# addonv2.net
KiCad netlist of a schematic drawn in EAGLE
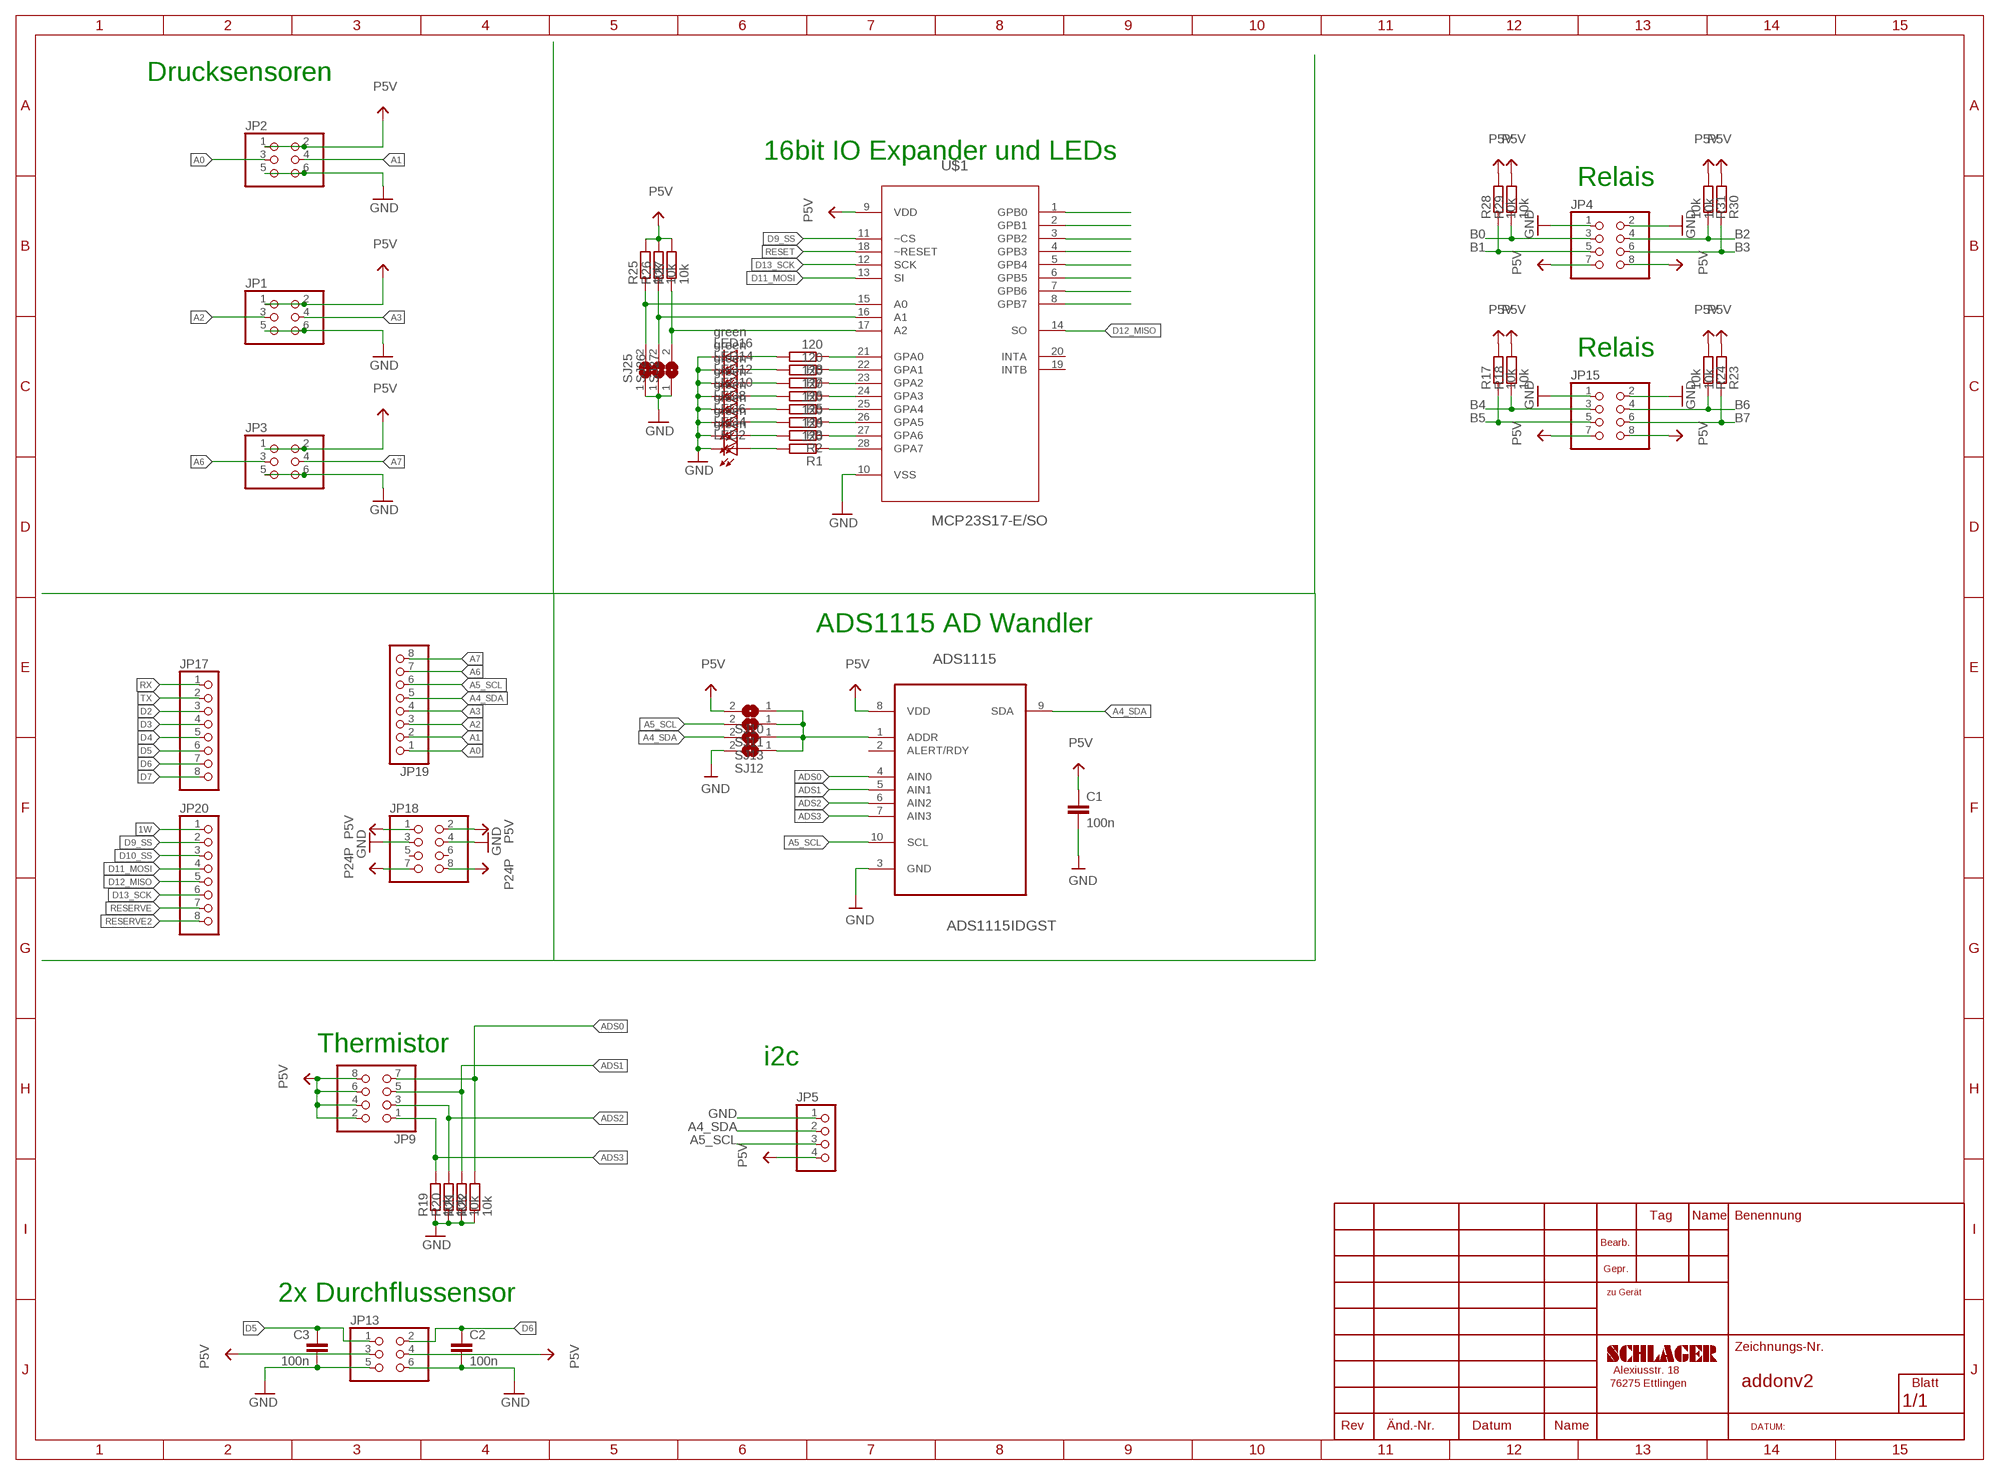
[diagram p0: schematic, sheet 1]

(export (version "E")
  (design (tool "Eeschema 10.0.6"))
  (components
    (comp (ref "ADS1115")
      (value "ADS1115IDGST")
      (footprint "eagle-import:SOP50P490X110-10N")
      (libsource (lib "eagle-import") (part "ADS1115IDGST"))
    )
    (comp (ref "C1")
      (value "100n")
      (footprint "eagle-import:C0805")
      (libsource (lib "eagle-import") (part "C-EUC0805"))
    )
    (comp (ref "C2")
      (value "100n")
      (footprint "eagle-import:C0805")
      (libsource (lib "eagle-import") (part "C-EUC0805"))
    )
    (comp (ref "C3")
      (value "100n")
      (footprint "eagle-import:C0805")
      (libsource (lib "eagle-import") (part "C-EUC0805"))
    )
    (comp (ref "JP1")
      (value "PINHD-2X3/90")
      (footprint "eagle-import:2X03_90")
      (libsource (lib "eagle-import") (part "PINHD-2X3/90"))
    )
    (comp (ref "JP2")
      (value "PINHD-2X3/90")
      (footprint "eagle-import:2X03_90")
      (libsource (lib "eagle-import") (part "PINHD-2X3/90"))
    )
    (comp (ref "JP3")
      (value "PINHD-2X3/90")
      (footprint "eagle-import:2X03_90")
      (libsource (lib "eagle-import") (part "PINHD-2X3/90"))
    )
    (comp (ref "JP4")
      (value "PINHD-2X4/90")
      (footprint "eagle-import:2X04_90")
      (libsource (lib "eagle-import") (part "PINHD-2X4/90"))
    )
    (comp (ref "JP5")
      (value "PINHD-1X4/90")
      (footprint "eagle-import:1X04_90")
      (libsource (lib "eagle-import") (part "PINHD-1X4/90"))
    )
    (comp (ref "JP9")
      (value "PINHD-2X4/90")
      (footprint "eagle-import:2X04_90")
      (libsource (lib "eagle-import") (part "PINHD-2X4/90"))
    )
    (comp (ref "JP13")
      (value "PINHD-2X3/90")
      (footprint "eagle-import:2X03_90")
      (libsource (lib "eagle-import") (part "PINHD-2X3/90"))
    )
    (comp (ref "JP15")
      (value "PINHD-2X4/90")
      (footprint "eagle-import:2X04_90")
      (libsource (lib "eagle-import") (part "PINHD-2X4/90"))
    )
    (comp (ref "JP17")
      (value "PINHD-1X8")
      (footprint "eagle-import:1X08")
      (libsource (lib "eagle-import") (part "PINHD-1X8"))
    )
    (comp (ref "JP18")
      (value "PINHD-2X4")
      (footprint "eagle-import:2X04")
      (libsource (lib "eagle-import") (part "PINHD-2X4"))
    )
    (comp (ref "JP19")
      (value "PINHD-1X8")
      (footprint "eagle-import:1X08")
      (libsource (lib "eagle-import") (part "PINHD-1X8"))
    )
    (comp (ref "JP20")
      (value "PINHD-1X8")
      (footprint "eagle-import:1X08")
      (libsource (lib "eagle-import") (part "PINHD-1X8"))
    )
    (comp (ref "LED2")
      (value "green")
      (footprint "eagle-import:CHIPLED_0805")
      (libsource (lib "eagle-import") (part "LEDCHIPLED_0805"))
    )
    (comp (ref "LED4")
      (value "green")
      (footprint "eagle-import:CHIPLED_0805")
      (libsource (lib "eagle-import") (part "LEDCHIPLED_0805"))
    )
    (comp (ref "LED6")
      (value "green")
      (footprint "eagle-import:CHIPLED_0805")
      (libsource (lib "eagle-import") (part "LEDCHIPLED_0805"))
    )
    (comp (ref "LED8")
      (value "green")
      (footprint "eagle-import:CHIPLED_0805")
      (libsource (lib "eagle-import") (part "LEDCHIPLED_0805"))
    )
    (comp (ref "LED10")
      (value "green")
      (footprint "eagle-import:CHIPLED_0805")
      (libsource (lib "eagle-import") (part "LEDCHIPLED_0805"))
    )
    (comp (ref "LED12")
      (value "green")
      (footprint "eagle-import:CHIPLED_0805")
      (libsource (lib "eagle-import") (part "LEDCHIPLED_0805"))
    )
    (comp (ref "LED14")
      (value "green")
      (footprint "eagle-import:CHIPLED_0805")
      (libsource (lib "eagle-import") (part "LEDCHIPLED_0805"))
    )
    (comp (ref "LED16")
      (value "green")
      (footprint "eagle-import:CHIPLED_0805")
      (libsource (lib "eagle-import") (part "LEDCHIPLED_0805"))
    )
    (comp (ref "R1")
      (value "120")
      (footprint "eagle-import:R0603")
      (libsource (lib "eagle-import") (part "R-EU_R0603"))
    )
    (comp (ref "R2")
      (value "120")
      (footprint "eagle-import:R0603")
      (libsource (lib "eagle-import") (part "R-EU_R0603"))
    )
    (comp (ref "R3")
      (value "120")
      (footprint "eagle-import:R0603")
      (libsource (lib "eagle-import") (part "R-EU_R0603"))
    )
    (comp (ref "R4")
      (value "120")
      (footprint "eagle-import:R0603")
      (libsource (lib "eagle-import") (part "R-EU_R0603"))
    )
    (comp (ref "R5")
      (value "120")
      (footprint "eagle-import:R0603")
      (libsource (lib "eagle-import") (part "R-EU_R0603"))
    )
    (comp (ref "R6")
      (value "120")
      (footprint "eagle-import:R0603")
      (libsource (lib "eagle-import") (part "R-EU_R0603"))
    )
    (comp (ref "R7")
      (value "120")
      (footprint "eagle-import:R0603")
      (libsource (lib "eagle-import") (part "R-EU_R0603"))
    )
    (comp (ref "R8")
      (value "120")
      (footprint "eagle-import:R0603")
      (libsource (lib "eagle-import") (part "R-EU_R0603"))
    )
    (comp (ref "R17")
      (value "10k")
      (footprint "eagle-import:R0603")
      (libsource (lib "eagle-import") (part "R-EU_R0603"))
    )
    (comp (ref "R18")
      (value "10k")
      (footprint "eagle-import:R0603")
      (libsource (lib "eagle-import") (part "R-EU_R0603"))
    )
    (comp (ref "R19")
      (value "10k")
      (footprint "eagle-import:R0603")
      (libsource (lib "eagle-import") (part "R-EU_R0603"))
    )
    (comp (ref "R20")
      (value "10k")
      (footprint "eagle-import:R0603")
      (libsource (lib "eagle-import") (part "R-EU_R0603"))
    )
    (comp (ref "R21")
      (value "10k")
      (footprint "eagle-import:R0603")
      (libsource (lib "eagle-import") (part "R-EU_R0603"))
    )
    (comp (ref "R22")
      (value "10k")
      (footprint "eagle-import:R0603")
      (libsource (lib "eagle-import") (part "R-EU_R0603"))
    )
    (comp (ref "R23")
      (value "10k")
      (footprint "eagle-import:R0603")
      (libsource (lib "eagle-import") (part "R-EU_R0603"))
    )
    (comp (ref "R24")
      (value "10k")
      (footprint "eagle-import:R0603")
      (libsource (lib "eagle-import") (part "R-EU_R0603"))
    )
    (comp (ref "R25")
      (value "10k")
      (footprint "eagle-import:R0603")
      (libsource (lib "eagle-import") (part "R-EU_R0603"))
    )
    (comp (ref "R26")
      (value "10k")
      (footprint "eagle-import:R0603")
      (libsource (lib "eagle-import") (part "R-EU_R0603"))
    )
    (comp (ref "R27")
      (value "10k")
      (footprint "eagle-import:R0603")
      (libsource (lib "eagle-import") (part "R-EU_R0603"))
    )
    (comp (ref "R28")
      (value "10k")
      (footprint "eagle-import:R0603")
      (libsource (lib "eagle-import") (part "R-EU_R0603"))
    )
    (comp (ref "R29")
      (value "10k")
      (footprint "eagle-import:R0603")
      (libsource (lib "eagle-import") (part "R-EU_R0603"))
    )
    (comp (ref "R30")
      (value "10k")
      (footprint "eagle-import:R0603")
      (libsource (lib "eagle-import") (part "R-EU_R0603"))
    )
    (comp (ref "R31")
      (value "10k")
      (footprint "eagle-import:R0603")
      (libsource (lib "eagle-import") (part "R-EU_R0603"))
    )
    (comp (ref "SJ10")
      (value "SJN")
      (footprint "eagle-import:SJ")
      (libsource (lib "eagle-import") (part "SJN"))
    )
    (comp (ref "SJ11")
      (value "SJN")
      (footprint "eagle-import:SJ")
      (libsource (lib "eagle-import") (part "SJN"))
    )
    (comp (ref "SJ12")
      (value "SJN")
      (footprint "eagle-import:SJ")
      (libsource (lib "eagle-import") (part "SJN"))
    )
    (comp (ref "SJ13")
      (value "SJN")
      (footprint "eagle-import:SJ")
      (libsource (lib "eagle-import") (part "SJN"))
    )
    (comp (ref "SJ25")
      (value "SJN")
      (footprint "eagle-import:SJ")
      (libsource (lib "eagle-import") (part "SJN"))
    )
    (comp (ref "SJ26")
      (value "SJN")
      (footprint "eagle-import:SJ")
      (libsource (lib "eagle-import") (part "SJN"))
    )
    (comp (ref "SJ27")
      (value "SJN")
      (footprint "eagle-import:SJ")
      (libsource (lib "eagle-import") (part "SJN"))
    )
    (comp (ref "U$1")
      (value "MCP23S17-E/SO")
      (footprint "eagle-import:SOIC127P030X265-28N")
      (libsource (lib "eagle-import") (part "MCP23S17-E/SO"))
    )
  )
  (nets
    (net (code "1") (name "/B0") (class "Default")
      (node (ref "JP4") (pin "3") (pinfunction "3_3") (pintype "passive"))
      (node (ref "R29") (pin "1") (pinfunction "1_1") (pintype "passive"))
      (node (ref "U$1") (pin "1") (pinfunction "GPB0_1") (pintype "bidirectional"))
    )
    (net (code "2") (name "/B1") (class "Default")
      (node (ref "JP4") (pin "5") (pinfunction "5_5") (pintype "passive"))
      (node (ref "R28") (pin "1") (pinfunction "1_1") (pintype "passive"))
      (node (ref "U$1") (pin "2") (pinfunction "GPB1_2") (pintype "bidirectional"))
    )
    (net (code "3") (name "/B2") (class "Default")
      (node (ref "JP4") (pin "4") (pinfunction "4_4") (pintype "passive"))
      (node (ref "R31") (pin "1") (pinfunction "1_1") (pintype "passive"))
      (node (ref "U$1") (pin "3") (pinfunction "GPB2_3") (pintype "bidirectional"))
    )
    (net (code "4") (name "/B3") (class "Default")
      (node (ref "JP4") (pin "6") (pinfunction "6_6") (pintype "passive"))
      (node (ref "R30") (pin "1") (pinfunction "1_1") (pintype "passive"))
      (node (ref "U$1") (pin "4") (pinfunction "GPB3_4") (pintype "bidirectional"))
    )
    (net (code "5") (name "/B4") (class "Default")
      (node (ref "JP15") (pin "3") (pinfunction "3_3") (pintype "passive"))
      (node (ref "R18") (pin "1") (pinfunction "1_1") (pintype "passive"))
      (node (ref "U$1") (pin "5") (pinfunction "GPB4_5") (pintype "bidirectional"))
    )
    (net (code "6") (name "/B5") (class "Default")
      (node (ref "JP15") (pin "5") (pinfunction "5_5") (pintype "passive"))
      (node (ref "R17") (pin "1") (pinfunction "1_1") (pintype "passive"))
      (node (ref "U$1") (pin "6") (pinfunction "GPB5_6") (pintype "bidirectional"))
    )
    (net (code "7") (name "/B6") (class "Default")
      (node (ref "JP15") (pin "4") (pinfunction "4_4") (pintype "passive"))
      (node (ref "R24") (pin "1") (pinfunction "1_1") (pintype "passive"))
      (node (ref "U$1") (pin "7") (pinfunction "GPB6_7") (pintype "bidirectional"))
    )
    (net (code "8") (name "/B7") (class "Default")
      (node (ref "JP15") (pin "6") (pinfunction "6_6") (pintype "passive"))
      (node (ref "R23") (pin "1") (pinfunction "1_1") (pintype "passive"))
      (node (ref "U$1") (pin "8") (pinfunction "GPB7_8") (pintype "bidirectional"))
    )
    (net (code "9") (name "1W") (class "Default")
      (node (ref "JP20") (pin "1") (pinfunction "1_1") (pintype "passive"))
    )
    (net (code "10") (name "A0") (class "Default")
      (node (ref "JP19") (pin "1") (pinfunction "1_1") (pintype "passive"))
      (node (ref "JP2") (pin "3") (pinfunction "3_3") (pintype "passive"))
    )
    (net (code "11") (name "A1") (class "Default")
      (node (ref "JP19") (pin "2") (pinfunction "2_2") (pintype "passive"))
      (node (ref "JP2") (pin "4") (pinfunction "4_4") (pintype "passive"))
    )
    (net (code "12") (name "A2") (class "Default")
      (node (ref "JP1") (pin "3") (pinfunction "3_3") (pintype "passive"))
      (node (ref "JP19") (pin "3") (pinfunction "3_3") (pintype "passive"))
    )
    (net (code "13") (name "A3") (class "Default")
      (node (ref "JP1") (pin "4") (pinfunction "4_4") (pintype "passive"))
      (node (ref "JP19") (pin "4") (pinfunction "4_4") (pintype "passive"))
    )
    (net (code "14") (name "A4_SDA") (class "Default")
      (node (ref "ADS1115") (pin "9") (pinfunction "SDA_9") (pintype "bidirectional"))
      (node (ref "JP19") (pin "5") (pinfunction "5_5") (pintype "passive"))
      (node (ref "JP5") (pin "2") (pinfunction "2_2") (pintype "passive"))
      (node (ref "SJ13") (pin "2") (pinfunction "2_2") (pintype "passive"))
    )
    (net (code "15") (name "A5_SCL") (class "Default")
      (node (ref "ADS1115") (pin "10") (pinfunction "SCL_10") (pintype "input"))
      (node (ref "JP19") (pin "6") (pinfunction "6_6") (pintype "passive"))
      (node (ref "JP5") (pin "3") (pinfunction "3_3") (pintype "passive"))
      (node (ref "SJ11") (pin "2") (pinfunction "2_2") (pintype "passive"))
    )
    (net (code "16") (name "A6") (class "Default")
      (node (ref "JP19") (pin "7") (pinfunction "7_7") (pintype "passive"))
      (node (ref "JP3") (pin "3") (pinfunction "3_3") (pintype "passive"))
    )
    (net (code "17") (name "A7") (class "Default")
      (node (ref "JP19") (pin "8") (pinfunction "8_8") (pintype "passive"))
      (node (ref "JP3") (pin "4") (pinfunction "4_4") (pintype "passive"))
    )
    (net (code "18") (name "ADS0") (class "Default")
      (node (ref "ADS1115") (pin "4") (pinfunction "AIN0_4") (pintype "input"))
      (node (ref "JP9") (pin "7") (pinfunction "7_7") (pintype "passive"))
      (node (ref "R22") (pin "2") (pinfunction "2_2") (pintype "passive"))
    )
    (net (code "19") (name "ADS1") (class "Default")
      (node (ref "ADS1115") (pin "5") (pinfunction "AIN1_5") (pintype "input"))
      (node (ref "JP9") (pin "5") (pinfunction "5_5") (pintype "passive"))
      (node (ref "R21") (pin "2") (pinfunction "2_2") (pintype "passive"))
    )
    (net (code "20") (name "ADS2") (class "Default")
      (node (ref "ADS1115") (pin "6") (pinfunction "AIN2_6") (pintype "input"))
      (node (ref "JP9") (pin "3") (pinfunction "3_3") (pintype "passive"))
      (node (ref "R20") (pin "2") (pinfunction "2_2") (pintype "passive"))
    )
    (net (code "21") (name "ADS3") (class "Default")
      (node (ref "ADS1115") (pin "7") (pinfunction "AIN3_7") (pintype "input"))
      (node (ref "JP9") (pin "1") (pinfunction "1_1") (pintype "passive"))
      (node (ref "R19") (pin "2") (pinfunction "2_2") (pintype "passive"))
    )
    (net (code "22") (name "D2") (class "Default")
      (node (ref "JP17") (pin "3") (pinfunction "3_3") (pintype "passive"))
    )
    (net (code "23") (name "D3") (class "Default")
      (node (ref "JP17") (pin "4") (pinfunction "4_4") (pintype "passive"))
    )
    (net (code "24") (name "D4") (class "Default")
      (node (ref "JP17") (pin "5") (pinfunction "5_5") (pintype "passive"))
    )
    (net (code "25") (name "D5") (class "Default")
      (node (ref "C3") (pin "1") (pinfunction "1_1") (pintype "passive"))
      (node (ref "JP13") (pin "1") (pinfunction "1_1") (pintype "passive"))
      (node (ref "JP17") (pin "6") (pinfunction "6_6") (pintype "passive"))
    )
    (net (code "26") (name "D6") (class "Default")
      (node (ref "C2") (pin "1") (pinfunction "1_1") (pintype "passive"))
      (node (ref "JP13") (pin "2") (pinfunction "2_2") (pintype "passive"))
      (node (ref "JP17") (pin "7") (pinfunction "7_7") (pintype "passive"))
    )
    (net (code "27") (name "D7") (class "Default")
      (node (ref "JP17") (pin "8") (pinfunction "8_8") (pintype "passive"))
    )
    (net (code "28") (name "D9_SS") (class "Default")
      (node (ref "JP20") (pin "2") (pinfunction "2_2") (pintype "passive"))
      (node (ref "U$1") (pin "11") (pinfunction "~{CS}_11") (pintype "input"))
    )
    (net (code "29") (name "D10_SS") (class "Default")
      (node (ref "JP20") (pin "3") (pinfunction "3_3") (pintype "passive"))
    )
    (net (code "30") (name "D11_MOSI") (class "Default")
      (node (ref "JP20") (pin "4") (pinfunction "4_4") (pintype "passive"))
      (node (ref "U$1") (pin "13") (pinfunction "SI_13") (pintype "input"))
    )
    (net (code "31") (name "D12_MISO") (class "Default")
      (node (ref "JP20") (pin "5") (pinfunction "5_5") (pintype "passive"))
      (node (ref "U$1") (pin "14") (pinfunction "SO_14") (pintype "output"))
    )
    (net (code "32") (name "D13_SCK") (class "Default")
      (node (ref "JP20") (pin "6") (pinfunction "6_6") (pintype "passive"))
      (node (ref "U$1") (pin "12") (pinfunction "SCK_12") (pintype "input"))
    )
    (net (code "33") (name "GND") (class "Default")
      (node (ref "ADS1115") (pin "3") (pinfunction "GND_3") (pintype "passive"))
      (node (ref "C1") (pin "2") (pinfunction "2_2") (pintype "passive"))
      (node (ref "C2") (pin "2") (pinfunction "2_2") (pintype "passive"))
      (node (ref "C3") (pin "2") (pinfunction "2_2") (pintype "passive"))
      (node (ref "JP1") (pin "5") (pinfunction "5_5") (pintype "passive"))
      (node (ref "JP1") (pin "6") (pinfunction "6_6") (pintype "passive"))
      (node (ref "JP13") (pin "5") (pinfunction "5_5") (pintype "passive"))
      (node (ref "JP13") (pin "6") (pinfunction "6_6") (pintype "passive"))
      (node (ref "JP15") (pin "1") (pinfunction "1_1") (pintype "passive"))
      (node (ref "JP15") (pin "2") (pinfunction "2_2") (pintype "passive"))
      (node (ref "JP18") (pin "3") (pinfunction "3_3") (pintype "passive"))
      (node (ref "JP18") (pin "4") (pinfunction "4_4") (pintype "passive"))
      (node (ref "JP2") (pin "5") (pinfunction "5_5") (pintype "passive"))
      (node (ref "JP2") (pin "6") (pinfunction "6_6") (pintype "passive"))
      (node (ref "JP3") (pin "5") (pinfunction "5_5") (pintype "passive"))
      (node (ref "JP3") (pin "6") (pinfunction "6_6") (pintype "passive"))
      (node (ref "JP4") (pin "1") (pinfunction "1_1") (pintype "passive"))
      (node (ref "JP4") (pin "2") (pinfunction "2_2") (pintype "passive"))
      (node (ref "JP5") (pin "1") (pinfunction "1_1") (pintype "passive"))
      (node (ref "LED10") (pin "C") (pinfunction "C_C") (pintype "passive"))
      (node (ref "LED12") (pin "C") (pinfunction "C_C") (pintype "passive"))
      (node (ref "LED14") (pin "C") (pinfunction "C_C") (pintype "passive"))
      (node (ref "LED16") (pin "C") (pinfunction "C_C") (pintype "passive"))
      (node (ref "LED2") (pin "C") (pinfunction "C_C") (pintype "passive"))
      (node (ref "LED4") (pin "C") (pinfunction "C_C") (pintype "passive"))
      (node (ref "LED6") (pin "C") (pinfunction "C_C") (pintype "passive"))
      (node (ref "LED8") (pin "C") (pinfunction "C_C") (pintype "passive"))
      (node (ref "R19") (pin "1") (pinfunction "1_1") (pintype "passive"))
      (node (ref "R20") (pin "1") (pinfunction "1_1") (pintype "passive"))
      (node (ref "R21") (pin "1") (pinfunction "1_1") (pintype "passive"))
      (node (ref "R22") (pin "1") (pinfunction "1_1") (pintype "passive"))
      (node (ref "SJ12") (pin "2") (pinfunction "2_2") (pintype "passive"))
      (node (ref "SJ25") (pin "1") (pinfunction "1_1") (pintype "passive"))
      (node (ref "SJ26") (pin "1") (pinfunction "1_1") (pintype "passive"))
      (node (ref "SJ27") (pin "1") (pinfunction "1_1") (pintype "passive"))
      (node (ref "U$1") (pin "10") (pinfunction "VSS_10") (pintype "power_in"))
    )
    (net (code "34") (name "Net-(ADS1115-ADDR)") (class "Default")
      (node (ref "ADS1115") (pin "1") (pinfunction "ADDR_1") (pintype "input"))
      (node (ref "SJ10") (pin "1") (pinfunction "1_1") (pintype "passive"))
      (node (ref "SJ11") (pin "1") (pinfunction "1_1") (pintype "passive"))
      (node (ref "SJ12") (pin "1") (pinfunction "1_1") (pintype "passive"))
      (node (ref "SJ13") (pin "1") (pinfunction "1_1") (pintype "passive"))
    )
    (net (code "35") (name "Net-(LED2-PadA)") (class "Default")
      (node (ref "LED2") (pin "A") (pinfunction "A_A") (pintype "passive"))
      (node (ref "R1") (pin "2") (pinfunction "2_2") (pintype "passive"))
    )
    (net (code "36") (name "Net-(LED4-PadA)") (class "Default")
      (node (ref "LED4") (pin "A") (pinfunction "A_A") (pintype "passive"))
      (node (ref "R2") (pin "2") (pinfunction "2_2") (pintype "passive"))
    )
    (net (code "37") (name "Net-(LED6-PadA)") (class "Default")
      (node (ref "LED6") (pin "A") (pinfunction "A_A") (pintype "passive"))
      (node (ref "R3") (pin "2") (pinfunction "2_2") (pintype "passive"))
    )
    (net (code "38") (name "Net-(LED8-PadA)") (class "Default")
      (node (ref "LED8") (pin "A") (pinfunction "A_A") (pintype "passive"))
      (node (ref "R4") (pin "2") (pinfunction "2_2") (pintype "passive"))
    )
    (net (code "39") (name "Net-(LED10-PadA)") (class "Default")
      (node (ref "LED10") (pin "A") (pinfunction "A_A") (pintype "passive"))
      (node (ref "R5") (pin "2") (pinfunction "2_2") (pintype "passive"))
    )
    (net (code "40") (name "Net-(LED12-PadA)") (class "Default")
      (node (ref "LED12") (pin "A") (pinfunction "A_A") (pintype "passive"))
      (node (ref "R6") (pin "2") (pinfunction "2_2") (pintype "passive"))
    )
    (net (code "41") (name "Net-(LED14-PadA)") (class "Default")
      (node (ref "LED14") (pin "A") (pinfunction "A_A") (pintype "passive"))
      (node (ref "R7") (pin "2") (pinfunction "2_2") (pintype "passive"))
    )
    (net (code "42") (name "Net-(LED16-PadA)") (class "Default")
      (node (ref "LED16") (pin "A") (pinfunction "A_A") (pintype "passive"))
      (node (ref "R8") (pin "2") (pinfunction "2_2") (pintype "passive"))
    )
    (net (code "43") (name "Net-(U$1-A0)") (class "Default")
      (node (ref "R25") (pin "1") (pinfunction "1_1") (pintype "passive"))
      (node (ref "SJ25") (pin "2") (pinfunction "2_2") (pintype "passive"))
      (node (ref "U$1") (pin "15") (pinfunction "A0_15") (pintype "input"))
    )
    (net (code "44") (name "Net-(U$1-A1)") (class "Default")
      (node (ref "R26") (pin "1") (pinfunction "1_1") (pintype "passive"))
      (node (ref "SJ26") (pin "2") (pinfunction "2_2") (pintype "passive"))
      (node (ref "U$1") (pin "16") (pinfunction "A1_16") (pintype "input"))
    )
    (net (code "45") (name "Net-(U$1-A2)") (class "Default")
      (node (ref "R27") (pin "1") (pinfunction "1_1") (pintype "passive"))
      (node (ref "SJ27") (pin "2") (pinfunction "2_2") (pintype "passive"))
      (node (ref "U$1") (pin "17") (pinfunction "A2_17") (pintype "input"))
    )
    (net (code "46") (name "Net-(U$1-GPA0)") (class "Default")
      (node (ref "R8") (pin "1") (pinfunction "1_1") (pintype "passive"))
      (node (ref "U$1") (pin "21") (pinfunction "GPA0_21") (pintype "bidirectional"))
    )
    (net (code "47") (name "Net-(U$1-GPA1)") (class "Default")
      (node (ref "R7") (pin "1") (pinfunction "1_1") (pintype "passive"))
      (node (ref "U$1") (pin "22") (pinfunction "GPA1_22") (pintype "bidirectional"))
    )
    (net (code "48") (name "Net-(U$1-GPA2)") (class "Default")
      (node (ref "R6") (pin "1") (pinfunction "1_1") (pintype "passive"))
      (node (ref "U$1") (pin "23") (pinfunction "GPA2_23") (pintype "bidirectional"))
    )
    (net (code "49") (name "Net-(U$1-GPA3)") (class "Default")
      (node (ref "R5") (pin "1") (pinfunction "1_1") (pintype "passive"))
      (node (ref "U$1") (pin "24") (pinfunction "GPA3_24") (pintype "bidirectional"))
    )
    (net (code "50") (name "Net-(U$1-GPA4)") (class "Default")
      (node (ref "R4") (pin "1") (pinfunction "1_1") (pintype "passive"))
      (node (ref "U$1") (pin "25") (pinfunction "GPA4_25") (pintype "bidirectional"))
    )
    (net (code "51") (name "Net-(U$1-GPA5)") (class "Default")
      (node (ref "R3") (pin "1") (pinfunction "1_1") (pintype "passive"))
      (node (ref "U$1") (pin "26") (pinfunction "GPA5_26") (pintype "bidirectional"))
    )
    (net (code "52") (name "Net-(U$1-GPA6)") (class "Default")
      (node (ref "R2") (pin "1") (pinfunction "1_1") (pintype "passive"))
      (node (ref "U$1") (pin "27") (pinfunction "GPA6_27") (pintype "bidirectional"))
    )
    (net (code "53") (name "Net-(U$1-GPA7)") (class "Default")
      (node (ref "R1") (pin "1") (pinfunction "1_1") (pintype "passive"))
      (node (ref "U$1") (pin "28") (pinfunction "GPA7_28") (pintype "bidirectional"))
    )
    (net (code "54") (name "P5V") (class "Default")
      (node (ref "ADS1115") (pin "8") (pinfunction "VDD_8") (pintype "power_in"))
      (node (ref "C1") (pin "1") (pinfunction "1_1") (pintype "passive"))
      (node (ref "JP1") (pin "1") (pinfunction "1_1") (pintype "passive"))
      (node (ref "JP1") (pin "2") (pinfunction "2_2") (pintype "passive"))
      (node (ref "JP13") (pin "3") (pinfunction "3_3") (pintype "passive"))
      (node (ref "JP13") (pin "4") (pinfunction "4_4") (pintype "passive"))
      (node (ref "JP15") (pin "7") (pinfunction "7_7") (pintype "passive"))
      (node (ref "JP15") (pin "8") (pinfunction "8_8") (pintype "passive"))
      (node (ref "JP18") (pin "1") (pinfunction "1_1") (pintype "passive"))
      (node (ref "JP18") (pin "2") (pinfunction "2_2") (pintype "passive"))
      (node (ref "JP2") (pin "1") (pinfunction "1_1") (pintype "passive"))
      (node (ref "JP2") (pin "2") (pinfunction "2_2") (pintype "passive"))
      (node (ref "JP3") (pin "1") (pinfunction "1_1") (pintype "passive"))
      (node (ref "JP3") (pin "2") (pinfunction "2_2") (pintype "passive"))
      (node (ref "JP4") (pin "7") (pinfunction "7_7") (pintype "passive"))
      (node (ref "JP4") (pin "8") (pinfunction "8_8") (pintype "passive"))
      (node (ref "JP5") (pin "4") (pinfunction "4_4") (pintype "passive"))
      (node (ref "JP9") (pin "2") (pinfunction "2_2") (pintype "passive"))
      (node (ref "JP9") (pin "4") (pinfunction "4_4") (pintype "passive"))
      (node (ref "JP9") (pin "6") (pinfunction "6_6") (pintype "passive"))
      (node (ref "JP9") (pin "8") (pinfunction "8_8") (pintype "passive"))
      (node (ref "R17") (pin "2") (pinfunction "2_2") (pintype "passive"))
      (node (ref "R18") (pin "2") (pinfunction "2_2") (pintype "passive"))
      (node (ref "R23") (pin "2") (pinfunction "2_2") (pintype "passive"))
      (node (ref "R24") (pin "2") (pinfunction "2_2") (pintype "passive"))
      (node (ref "R25") (pin "2") (pinfunction "2_2") (pintype "passive"))
      (node (ref "R26") (pin "2") (pinfunction "2_2") (pintype "passive"))
      (node (ref "R27") (pin "2") (pinfunction "2_2") (pintype "passive"))
      (node (ref "R28") (pin "2") (pinfunction "2_2") (pintype "passive"))
      (node (ref "R29") (pin "2") (pinfunction "2_2") (pintype "passive"))
      (node (ref "R30") (pin "2") (pinfunction "2_2") (pintype "passive"))
      (node (ref "R31") (pin "2") (pinfunction "2_2") (pintype "passive"))
      (node (ref "SJ10") (pin "2") (pinfunction "2_2") (pintype "passive"))
      (node (ref "U$1") (pin "9") (pinfunction "VDD_9") (pintype "power_in"))
    )
    (net (code "55") (name "P24P") (class "Default")
      (node (ref "JP18") (pin "7") (pinfunction "7_7") (pintype "passive"))
      (node (ref "JP18") (pin "8") (pinfunction "8_8") (pintype "passive"))
    )
    (net (code "56") (name "RESERVE") (class "Default")
      (node (ref "JP20") (pin "7") (pinfunction "7_7") (pintype "passive"))
    )
    (net (code "57") (name "RESERVE2") (class "Default")
      (node (ref "JP20") (pin "8") (pinfunction "8_8") (pintype "passive"))
    )
    (net (code "58") (name "RESET") (class "Default")
      (node (ref "U$1") (pin "18") (pinfunction "~{RESET}_18") (pintype "input"))
    )
    (net (code "59") (name "RX") (class "Default")
      (node (ref "JP17") (pin "1") (pinfunction "1_1") (pintype "passive"))
    )
    (net (code "60") (name "TX") (class "Default")
      (node (ref "JP17") (pin "2") (pinfunction "2_2") (pintype "passive"))
    )
    (net (code "61") (name "unconnected-(ADS1115-ALERT{slash}RDY-Pad2)") (class "Default")
      (node (ref "ADS1115") (pin "2") (pinfunction "ALERT/RDY_2") (pintype "input"))
    )
    (net (code "62") (name "unconnected-(JP18-Pad5)") (class "Default")
      (node (ref "JP18") (pin "5") (pinfunction "5_5") (pintype "passive"))
    )
    (net (code "63") (name "unconnected-(JP18-Pad6)") (class "Default")
      (node (ref "JP18") (pin "6") (pinfunction "6_6") (pintype "passive"))
    )
    (net (code "64") (name "unconnected-(U$1-INTA-Pad20)") (class "Default")
      (node (ref "U$1") (pin "20") (pinfunction "INTA_20") (pintype "output"))
    )
    (net (code "65") (name "unconnected-(U$1-INTB-Pad19)") (class "Default")
      (node (ref "U$1") (pin "19") (pinfunction "INTB_19") (pintype "output"))
    )
  )
)
